# AVR8-pin.net
KiCad netlist of a schematic drawn in EAGLE
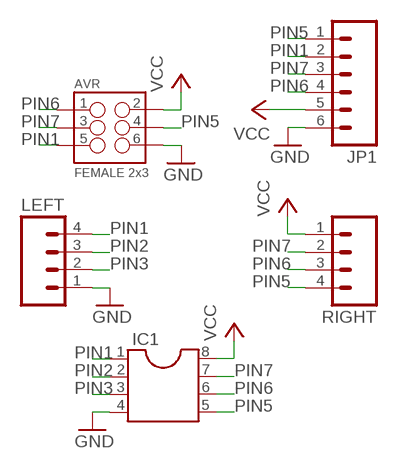
[diagram p0: schematic, sheet 1]

(export (version "E")
  (design (tool "Eeschema 10.0.6"))
  (components
    (comp (ref "AVR")
      (value "FEMALE 2x3")
      (footprint "eagle-import:2X3")
      (libsource (lib "eagle-import") (part "M03X2FEMALE"))
    )
    (comp (ref "IC1")
      (value "DIL8")
      (footprint "eagle-import:DIL08")
      (libsource (lib "eagle-import") (part "DIL8"))
    )
    (comp (ref "JP1")
      (value "M06SILK_FEMALE_PTH")
      (footprint "eagle-import:1X06")
      (libsource (lib "eagle-import") (part "M06SILK_FEMALE_PTH"))
    )
    (comp (ref "LEFT")
      (value "M04PTH")
      (footprint "eagle-import:1X04")
      (libsource (lib "eagle-import") (part "M04PTH"))
    )
    (comp (ref "RIGHT")
      (value "M04PTH")
      (footprint "eagle-import:1X04")
      (libsource (lib "eagle-import") (part "M04PTH"))
    )
  )
  (nets
    (net (code "1") (name "/PIN1") (class "Default")
      (node (ref "AVR") (pin "5") (pinfunction "5_5") (pintype "bidirectional"))
      (node (ref "IC1") (pin "1") (pinfunction "1_1") (pintype "passive"))
      (node (ref "JP1") (pin "2") (pinfunction "2_2") (pintype "passive"))
      (node (ref "LEFT") (pin "4") (pinfunction "4_4") (pintype "passive"))
    )
    (net (code "2") (name "/PIN2") (class "Default")
      (node (ref "IC1") (pin "2") (pinfunction "2_2") (pintype "passive"))
      (node (ref "LEFT") (pin "3") (pinfunction "3_3") (pintype "passive"))
    )
    (net (code "3") (name "/PIN3") (class "Default")
      (node (ref "IC1") (pin "3") (pinfunction "3_3") (pintype "passive"))
      (node (ref "LEFT") (pin "2") (pinfunction "2_2") (pintype "passive"))
    )
    (net (code "4") (name "/PIN5") (class "Default")
      (node (ref "AVR") (pin "4") (pinfunction "4_4") (pintype "bidirectional"))
      (node (ref "IC1") (pin "5") (pinfunction "5_5") (pintype "passive"))
      (node (ref "JP1") (pin "1") (pinfunction "1_1") (pintype "passive"))
      (node (ref "RIGHT") (pin "4") (pinfunction "4_4") (pintype "passive"))
    )
    (net (code "5") (name "/PIN6") (class "Default")
      (node (ref "AVR") (pin "1") (pinfunction "1_1") (pintype "bidirectional"))
      (node (ref "IC1") (pin "6") (pinfunction "6_6") (pintype "passive"))
      (node (ref "JP1") (pin "4") (pinfunction "4_4") (pintype "passive"))
      (node (ref "RIGHT") (pin "3") (pinfunction "3_3") (pintype "passive"))
    )
    (net (code "6") (name "/PIN7") (class "Default")
      (node (ref "AVR") (pin "3") (pinfunction "3_3") (pintype "bidirectional"))
      (node (ref "IC1") (pin "7") (pinfunction "7_7") (pintype "passive"))
      (node (ref "JP1") (pin "3") (pinfunction "3_3") (pintype "passive"))
      (node (ref "RIGHT") (pin "2") (pinfunction "2_2") (pintype "passive"))
    )
    (net (code "7") (name "GND") (class "Default")
      (node (ref "AVR") (pin "6") (pinfunction "6_6") (pintype "bidirectional"))
      (node (ref "IC1") (pin "4") (pinfunction "4_4") (pintype "passive"))
      (node (ref "JP1") (pin "6") (pinfunction "6_6") (pintype "passive"))
      (node (ref "LEFT") (pin "1") (pinfunction "1_1") (pintype "passive"))
    )
    (net (code "8") (name "VCC") (class "Default")
      (node (ref "AVR") (pin "2") (pinfunction "2_2") (pintype "bidirectional"))
      (node (ref "IC1") (pin "8") (pinfunction "8_8") (pintype "passive"))
      (node (ref "JP1") (pin "5") (pinfunction "5_5") (pintype "passive"))
      (node (ref "RIGHT") (pin "1") (pinfunction "1_1") (pintype "passive"))
    )
  )
)
